# EP4CE6E22C8N.net
KiCad netlist of a schematic drawn in Altium Designer
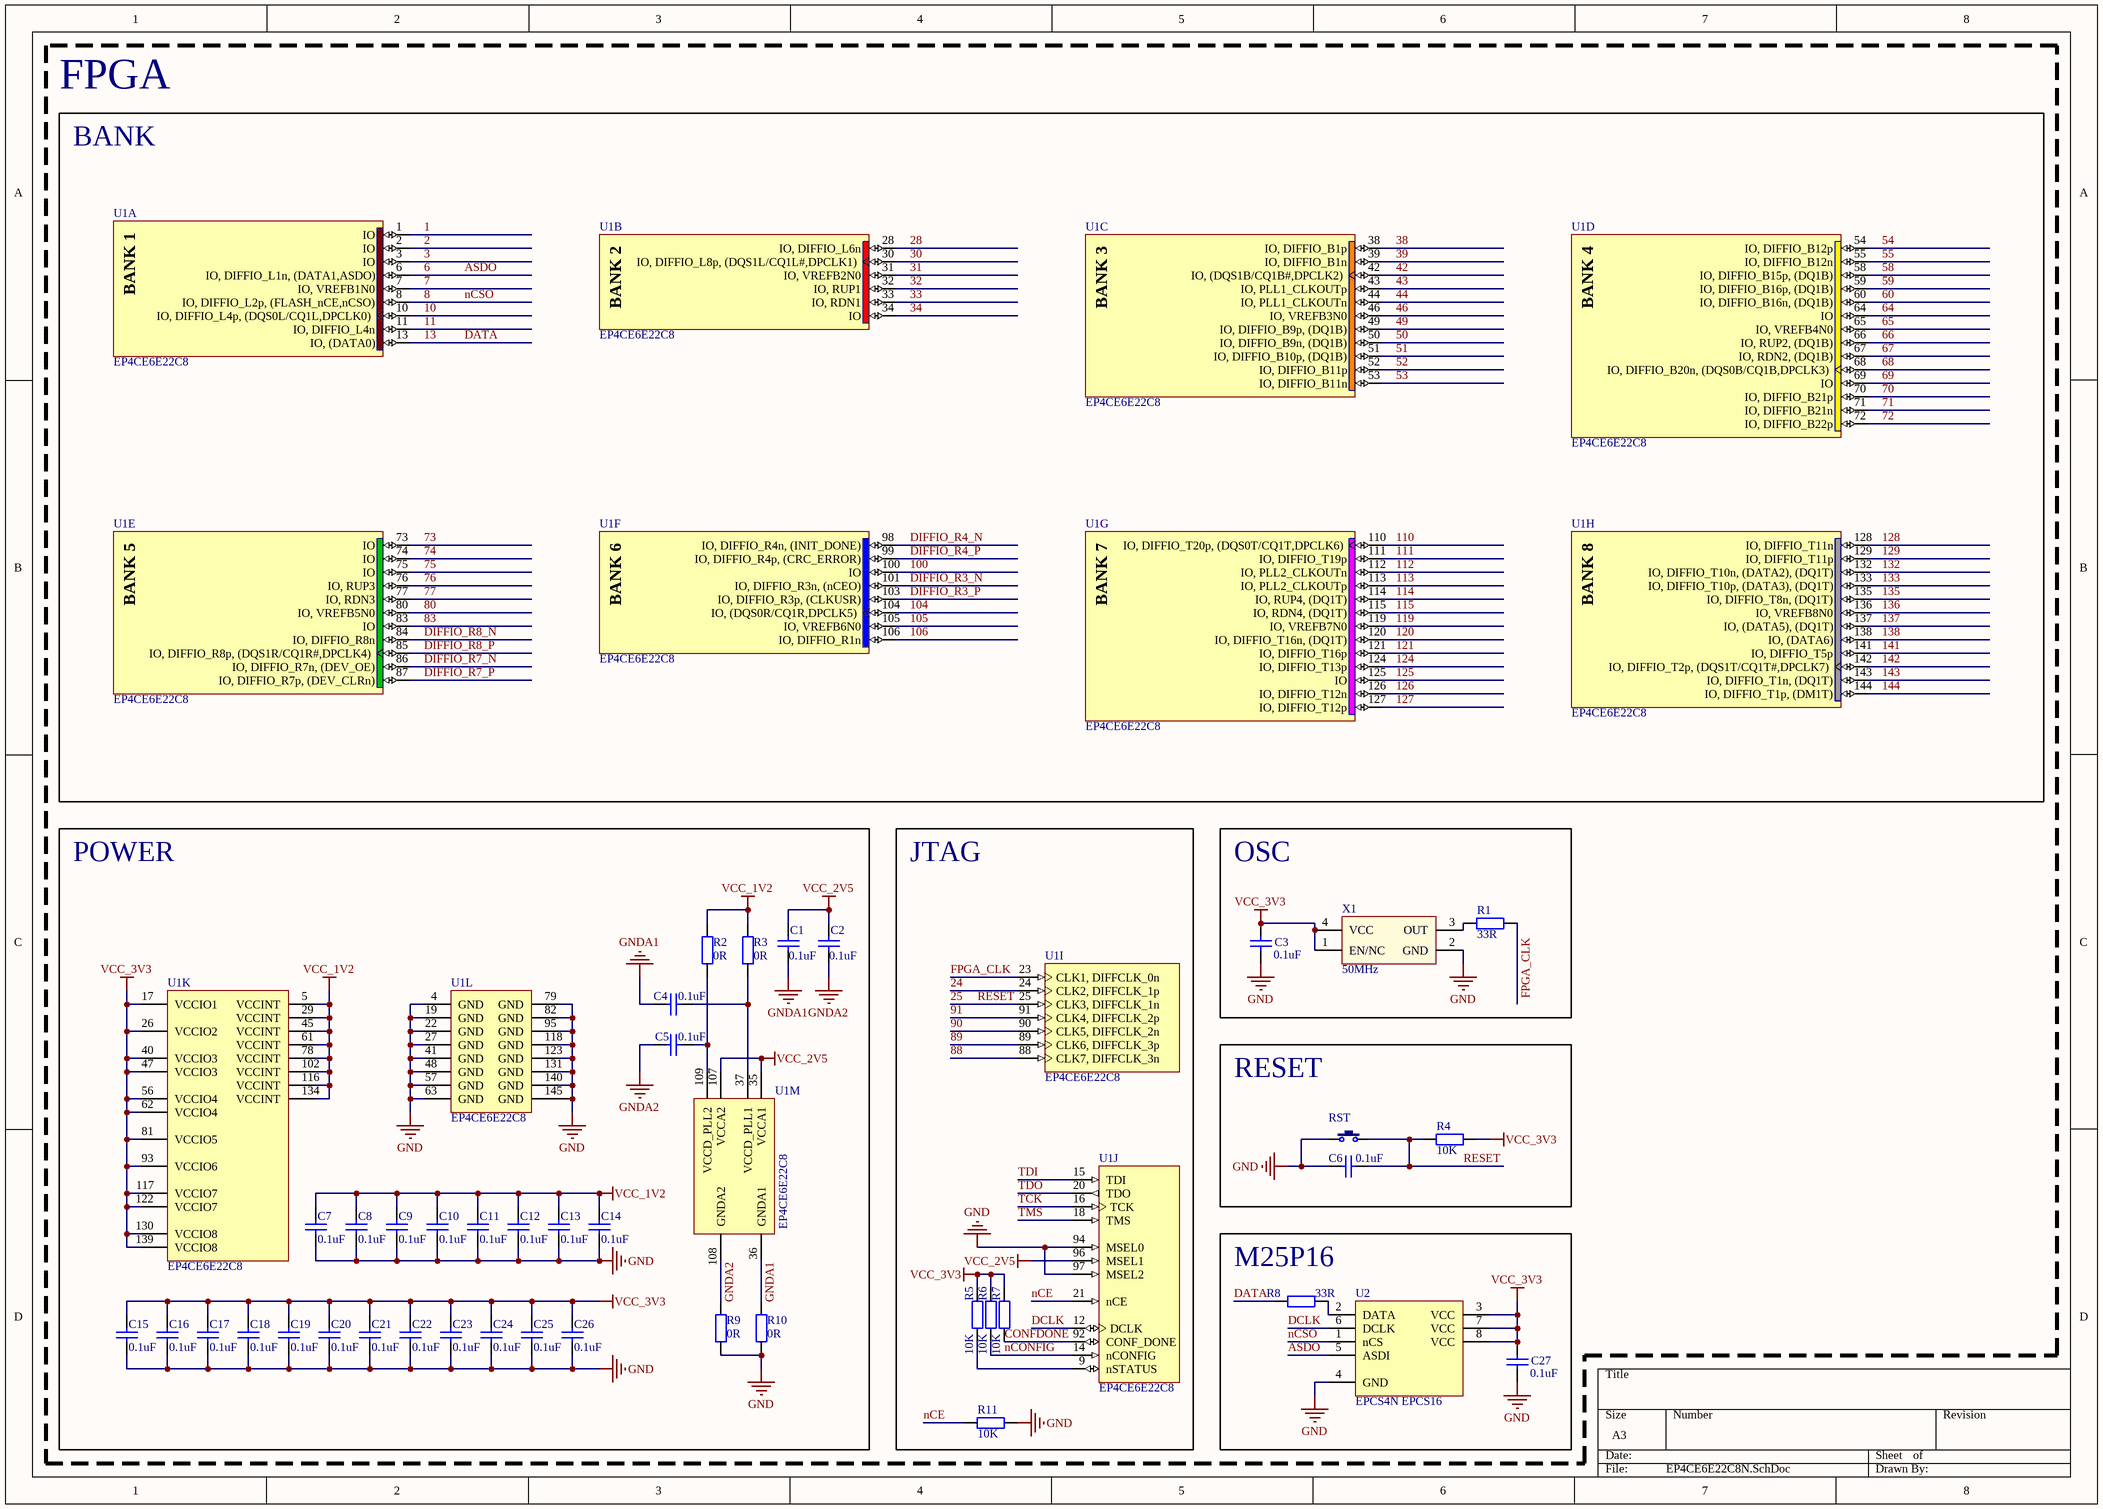
[diagram p0: EP4CE6E22C8N.SchDoc]

(export (version "E")
  (design (tool "Eeschema 10.0.6"))
  (components
    (comp (ref "C1")
      (value "0.1uF")
      (footprint "0402_C")
      (description "贴片电容")
      (libsource (lib "My_Devices") (part "0402_C"))
    )
    (comp (ref "C2")
      (value "0.1uF")
      (footprint "0402_C")
      (description "贴片电容")
      (libsource (lib "My_Devices") (part "0402_C"))
    )
    (comp (ref "C3")
      (value "0.1uF")
      (footprint "0402_C")
      (description "贴片电容")
      (libsource (lib "My_Devices") (part "0402_C"))
    )
    (comp (ref "C4")
      (value "0.1uF")
      (footprint "0402_C")
      (description "贴片电容")
      (libsource (lib "My_Devices") (part "0402_C"))
    )
    (comp (ref "C5")
      (value "0.1uF")
      (footprint "0402_C")
      (description "贴片电容")
      (libsource (lib "My_Devices") (part "0402_C"))
    )
    (comp (ref "C6")
      (value "0.1uF")
      (footprint "0402_C")
      (description "贴片电容")
      (libsource (lib "My_Devices") (part "0402_C"))
    )
    (comp (ref "C7")
      (value "0.1uF")
      (footprint "0402_C")
      (description "贴片电容")
      (libsource (lib "My_Devices") (part "0402_C"))
    )
    (comp (ref "C8")
      (value "0.1uF")
      (footprint "0402_C")
      (description "贴片电容")
      (libsource (lib "My_Devices") (part "0402_C"))
    )
    (comp (ref "C9")
      (value "0.1uF")
      (footprint "0402_C")
      (description "贴片电容")
      (libsource (lib "My_Devices") (part "0402_C"))
    )
    (comp (ref "C10")
      (value "0.1uF")
      (footprint "0402_C")
      (description "贴片电容")
      (libsource (lib "My_Devices") (part "0402_C"))
    )
    (comp (ref "C11")
      (value "0.1uF")
      (footprint "0402_C")
      (description "贴片电容")
      (libsource (lib "My_Devices") (part "0402_C"))
    )
    (comp (ref "C12")
      (value "0.1uF")
      (footprint "0402_C")
      (description "贴片电容")
      (libsource (lib "My_Devices") (part "0402_C"))
    )
    (comp (ref "C13")
      (value "0.1uF")
      (footprint "0402_C")
      (description "贴片电容")
      (libsource (lib "My_Devices") (part "0402_C"))
    )
    (comp (ref "C14")
      (value "0.1uF")
      (footprint "0402_C")
      (description "贴片电容")
      (libsource (lib "My_Devices") (part "0402_C"))
    )
    (comp (ref "C15")
      (value "0.1uF")
      (footprint "0402_C")
      (description "贴片电容")
      (libsource (lib "My_Devices") (part "0402_C"))
    )
    (comp (ref "C16")
      (value "0.1uF")
      (footprint "0402_C")
      (description "贴片电容")
      (libsource (lib "My_Devices") (part "0402_C"))
    )
    (comp (ref "C17")
      (value "0.1uF")
      (footprint "0402_C")
      (description "贴片电容")
      (libsource (lib "My_Devices") (part "0402_C"))
    )
    (comp (ref "C18")
      (value "0.1uF")
      (footprint "0402_C")
      (description "贴片电容")
      (libsource (lib "My_Devices") (part "0402_C"))
    )
    (comp (ref "C19")
      (value "0.1uF")
      (footprint "0402_C")
      (description "贴片电容")
      (libsource (lib "My_Devices") (part "0402_C"))
    )
    (comp (ref "C20")
      (value "0.1uF")
      (footprint "0402_C")
      (description "贴片电容")
      (libsource (lib "My_Devices") (part "0402_C"))
    )
    (comp (ref "C21")
      (value "0.1uF")
      (footprint "0402_C")
      (description "贴片电容")
      (libsource (lib "My_Devices") (part "0402_C"))
    )
    (comp (ref "C22")
      (value "0.1uF")
      (footprint "0402_C")
      (description "贴片电容")
      (libsource (lib "My_Devices") (part "0402_C"))
    )
    (comp (ref "C23")
      (value "0.1uF")
      (footprint "0402_C")
      (description "贴片电容")
      (libsource (lib "My_Devices") (part "0402_C"))
    )
    (comp (ref "C24")
      (value "0.1uF")
      (footprint "0402_C")
      (description "贴片电容")
      (libsource (lib "My_Devices") (part "0402_C"))
    )
    (comp (ref "C25")
      (value "0.1uF")
      (footprint "0402_C")
      (description "贴片电容")
      (libsource (lib "My_Devices") (part "0402_C"))
    )
    (comp (ref "C26")
      (value "0.1uF")
      (footprint "0402_C")
      (description "贴片电容")
      (libsource (lib "My_Devices") (part "0402_C"))
    )
    (comp (ref "C27")
      (value "0.1uF")
      (footprint "0402_C")
      (description "贴片电容")
      (libsource (lib "My_Devices") (part "0402_C"))
    )
    (comp (ref "R1")
      (value "33R")
      (footprint "0402_R")
      (description "贴片电阻")
      (libsource (lib "My_Devices") (part "0402_R"))
    )
    (comp (ref "R2")
      (value "0R")
      (footprint "0603_R _MINI")
      (description "贴片电阻")
      (libsource (lib "My_Devices") (part "0603_R_MINI"))
    )
    (comp (ref "R3")
      (value "0R")
      (footprint "0603_R _MINI")
      (description "贴片电阻")
      (libsource (lib "My_Devices") (part "0603_R_MINI"))
    )
    (comp (ref "R4")
      (value "10K")
      (footprint "0402_R")
      (description "贴片电阻")
      (libsource (lib "My_Devices") (part "0402_R"))
    )
    (comp (ref "R5")
      (value "10K")
      (footprint "0402_R")
      (description "贴片电阻")
      (libsource (lib "") (part "0402_R_1"))
    )
    (comp (ref "R6")
      (value "10K")
      (footprint "0402_R")
      (description "贴片电阻")
      (libsource (lib "") (part "0402_R_1"))
    )
    (comp (ref "R7")
      (value "10K")
      (footprint "0402_R")
      (description "贴片电阻")
      (libsource (lib "") (part "0402_R_1"))
    )
    (comp (ref "R8")
      (value "33R")
      (footprint "0402_R")
      (description "贴片电阻")
      (libsource (lib "My_Devices") (part "0402_R"))
    )
    (comp (ref "R9")
      (value "0R")
      (footprint "0603_R _MINI")
      (description "贴片电阻")
      (libsource (lib "My_Devices") (part "0603_R_MINI"))
    )
    (comp (ref "R10")
      (value "0R")
      (footprint "0603_R _MINI")
      (description "贴片电阻")
      (libsource (lib "My_Devices") (part "0603_R_MINI"))
    )
    (comp (ref "R11")
      (value "10K")
      (footprint "0402_R")
      (description "贴片电阻")
      (libsource (lib "My_Devices") (part "0402_R"))
    )
    (comp (ref "RST")
      (value "3x6x5")
      (footprint "SW")
      (description "3x6轻触开关")
      (fields (field (name "版权归属") "源创客"))
      (libsource (lib "My_Devices") (part "TSW 3x6"))
    )
    (comp (ref "U1")
      (value "EP4CE6E22C8")
      (footprint "EQFP144 20X20_N")
      (description "Cyclone IV Family FPGA, 2V Core, 91 I/O Pins, 2 PLLs, 144-Pin QFP, Speed Grade 8, Commercial Grade")
      (fields (field (name "PUBLISHER") "Altium Limited"))
      (libsource (lib "") (part "EP4CE6E22C8_1"))
    )
    (comp (ref "U2") (value "EPCS4N EPCS16") (footprint "SOP8_M") (libsource (lib "Schlib1") (part "EPCS1")))
    (comp (ref "X1")
      (value "50MHz")
      (footprint "OSC 7050-4P")
      (description "4脚有源晶振")
      (fields (field (name "版权归属") "源创客"))
      (libsource (lib "My_Devices") (part "XTAL-ACT-4P"))
    )
  )
  (nets
    (net (code "1") (name "/1") (class "Default")
      (node (ref "U1") (pin "1") (pinfunction "IO_1") (pintype "bidirectional"))
    )
    (net (code "2") (name "/2") (class "Default")
      (node (ref "U1") (pin "2") (pinfunction "IO_2") (pintype "bidirectional"))
    )
    (net (code "3") (name "/3") (class "Default")
      (node (ref "U1") (pin "3") (pinfunction "IO_3") (pintype "bidirectional"))
    )
    (net (code "4") (name "/6") (class "Default")
      (node (ref "U1") (pin "6") (pinfunction "IO,_DIFFIO_L1n,_(DATA1,ASDO)_6") (pintype "bidirectional"))
      (node (ref "U2") (pin "5") (pinfunction "ASDI_5") (pintype "passive"))
    )
    (net (code "5") (name "/7") (class "Default")
      (node (ref "U1") (pin "7") (pinfunction "IO,_VREFB1N0_7") (pintype "bidirectional"))
    )
    (net (code "6") (name "/8") (class "Default")
      (node (ref "U1") (pin "8") (pinfunction "IO,_DIFFIO_L2p,_(FLASH_nCE,nCSO)_8") (pintype "bidirectional"))
      (node (ref "U2") (pin "1") (pinfunction "nCS_1") (pintype "passive"))
    )
    (net (code "7") (name "/10") (class "Default")
      (node (ref "U1") (pin "10") (pinfunction "IO,_DIFFIO_L4p,_(DQS0L/CQ1L,DPCLK0)_10") (pintype "bidirectional"))
    )
    (net (code "8") (name "/11") (class "Default")
      (node (ref "U1") (pin "11") (pinfunction "IO,_DIFFIO_L4n_11") (pintype "bidirectional"))
    )
    (net (code "9") (name "/13") (class "Default")
      (node (ref "R8") (pin "1") (pinfunction "1_1") (pintype "passive"))
      (node (ref "U1") (pin "13") (pinfunction "IO,_(DATA0)_13") (pintype "bidirectional"))
    )
    (net (code "10") (name "/24") (class "Default")
      (node (ref "U1") (pin "24") (pinfunction "CLK2,_DIFFCLK_1p_24") (pintype "input"))
    )
    (net (code "11") (name "/25") (class "Default")
      (node (ref "C6") (pin "2") (pinfunction "2_2") (pintype "passive"))
      (node (ref "R4") (pin "1") (pinfunction "1_1") (pintype "passive"))
      (node (ref "RST") (pin "2") (pinfunction "2_2") (pintype "passive"))
      (node (ref "U1") (pin "25") (pinfunction "CLK3,_DIFFCLK_1n_25") (pintype "input"))
    )
    (net (code "12") (name "/28") (class "Default")
      (node (ref "U1") (pin "28") (pinfunction "IO,_DIFFIO_L6n_28") (pintype "bidirectional"))
    )
    (net (code "13") (name "/30") (class "Default")
      (node (ref "U1") (pin "30") (pinfunction "IO,_DIFFIO_L8p,_(DQS1L/CQ1L#,DPCLK1)_30") (pintype "bidirectional"))
    )
    (net (code "14") (name "/31") (class "Default")
      (node (ref "U1") (pin "31") (pinfunction "IO,_VREFB2N0_31") (pintype "bidirectional"))
    )
    (net (code "15") (name "/32") (class "Default")
      (node (ref "U1") (pin "32") (pinfunction "IO,_RUP1_32") (pintype "bidirectional"))
    )
    (net (code "16") (name "/33") (class "Default")
      (node (ref "U1") (pin "33") (pinfunction "IO,_RDN1_33") (pintype "bidirectional"))
    )
    (net (code "17") (name "/34") (class "Default")
      (node (ref "U1") (pin "34") (pinfunction "IO_34") (pintype "bidirectional"))
    )
    (net (code "18") (name "/38") (class "Default")
      (node (ref "U1") (pin "38") (pinfunction "IO,_DIFFIO_B1p_38") (pintype "bidirectional"))
    )
    (net (code "19") (name "/39") (class "Default")
      (node (ref "U1") (pin "39") (pinfunction "IO,_DIFFIO_B1n_39") (pintype "bidirectional"))
    )
    (net (code "20") (name "/42") (class "Default")
      (node (ref "U1") (pin "42") (pinfunction "IO,_(DQS1B/CQ1B#,DPCLK2)_42") (pintype "bidirectional"))
    )
    (net (code "21") (name "/43") (class "Default")
      (node (ref "U1") (pin "43") (pinfunction "IO,_PLL1_CLKOUTp_43") (pintype "bidirectional"))
    )
    (net (code "22") (name "/44") (class "Default")
      (node (ref "U1") (pin "44") (pinfunction "IO,_PLL1_CLKOUTn_44") (pintype "bidirectional"))
    )
    (net (code "23") (name "/46") (class "Default")
      (node (ref "U1") (pin "46") (pinfunction "IO,_VREFB3N0_46") (pintype "bidirectional"))
    )
    (net (code "24") (name "/49") (class "Default")
      (node (ref "U1") (pin "49") (pinfunction "IO,_DIFFIO_B9p,_(DQ1B)_49") (pintype "bidirectional"))
    )
    (net (code "25") (name "/50") (class "Default")
      (node (ref "U1") (pin "50") (pinfunction "IO,_DIFFIO_B9n,_(DQ1B)_50") (pintype "bidirectional"))
    )
    (net (code "26") (name "/51") (class "Default")
      (node (ref "U1") (pin "51") (pinfunction "IO,_DIFFIO_B10p,_(DQ1B)_51") (pintype "bidirectional"))
    )
    (net (code "27") (name "/52") (class "Default")
      (node (ref "U1") (pin "52") (pinfunction "IO,_DIFFIO_B11p_52") (pintype "bidirectional"))
    )
    (net (code "28") (name "/53") (class "Default")
      (node (ref "U1") (pin "53") (pinfunction "IO,_DIFFIO_B11n_53") (pintype "bidirectional"))
    )
    (net (code "29") (name "/54") (class "Default")
      (node (ref "U1") (pin "54") (pinfunction "IO,_DIFFIO_B12p_54") (pintype "bidirectional"))
    )
    (net (code "30") (name "/55") (class "Default")
      (node (ref "U1") (pin "55") (pinfunction "IO,_DIFFIO_B12n_55") (pintype "bidirectional"))
    )
    (net (code "31") (name "/58") (class "Default")
      (node (ref "U1") (pin "58") (pinfunction "IO,_DIFFIO_B15p,_(DQ1B)_58") (pintype "bidirectional"))
    )
    (net (code "32") (name "/59") (class "Default")
      (node (ref "U1") (pin "59") (pinfunction "IO,_DIFFIO_B16p,_(DQ1B)_59") (pintype "bidirectional"))
    )
    (net (code "33") (name "/60") (class "Default")
      (node (ref "U1") (pin "60") (pinfunction "IO,_DIFFIO_B16n,_(DQ1B)_60") (pintype "bidirectional"))
    )
    (net (code "34") (name "/64") (class "Default")
      (node (ref "U1") (pin "64") (pinfunction "IO_64") (pintype "bidirectional"))
    )
    (net (code "35") (name "/65") (class "Default")
      (node (ref "U1") (pin "65") (pinfunction "IO,_VREFB4N0_65") (pintype "bidirectional"))
    )
    (net (code "36") (name "/66") (class "Default")
      (node (ref "U1") (pin "66") (pinfunction "IO,_RUP2,_(DQ1B)_66") (pintype "bidirectional"))
    )
    (net (code "37") (name "/67") (class "Default")
      (node (ref "U1") (pin "67") (pinfunction "IO,_RDN2,_(DQ1B)_67") (pintype "bidirectional"))
    )
    (net (code "38") (name "/68") (class "Default")
      (node (ref "U1") (pin "68") (pinfunction "IO,_DIFFIO_B20n,_(DQS0B/CQ1B,DPCLK3)_68") (pintype "bidirectional"))
    )
    (net (code "39") (name "/69") (class "Default")
      (node (ref "U1") (pin "69") (pinfunction "IO_69") (pintype "bidirectional"))
    )
    (net (code "40") (name "/70") (class "Default")
      (node (ref "U1") (pin "70") (pinfunction "IO,_DIFFIO_B21p_70") (pintype "bidirectional"))
    )
    (net (code "41") (name "/71") (class "Default")
      (node (ref "U1") (pin "71") (pinfunction "IO,_DIFFIO_B21n_71") (pintype "bidirectional"))
    )
    (net (code "42") (name "/72") (class "Default")
      (node (ref "U1") (pin "72") (pinfunction "IO,_DIFFIO_B22p_72") (pintype "bidirectional"))
    )
    (net (code "43") (name "/73") (class "Default")
      (node (ref "U1") (pin "73") (pinfunction "IO_73") (pintype "bidirectional"))
    )
    (net (code "44") (name "/74") (class "Default")
      (node (ref "U1") (pin "74") (pinfunction "IO_74") (pintype "bidirectional"))
    )
    (net (code "45") (name "/75") (class "Default")
      (node (ref "U1") (pin "75") (pinfunction "IO_75") (pintype "bidirectional"))
    )
    (net (code "46") (name "/76") (class "Default")
      (node (ref "U1") (pin "76") (pinfunction "IO,_RUP3_76") (pintype "bidirectional"))
    )
    (net (code "47") (name "/77") (class "Default")
      (node (ref "U1") (pin "77") (pinfunction "IO,_RDN3_77") (pintype "bidirectional"))
    )
    (net (code "48") (name "/80") (class "Default")
      (node (ref "U1") (pin "80") (pinfunction "IO,_VREFB5N0_80") (pintype "bidirectional"))
    )
    (net (code "49") (name "/83") (class "Default")
      (node (ref "U1") (pin "83") (pinfunction "IO_83") (pintype "bidirectional"))
    )
    (net (code "50") (name "/88") (class "Default")
      (node (ref "U1") (pin "88") (pinfunction "CLK7,_DIFFCLK_3n_88") (pintype "input"))
    )
    (net (code "51") (name "/89") (class "Default")
      (node (ref "U1") (pin "89") (pinfunction "CLK6,_DIFFCLK_3p_89") (pintype "input"))
    )
    (net (code "52") (name "/90") (class "Default")
      (node (ref "U1") (pin "90") (pinfunction "CLK5,_DIFFCLK_2n_90") (pintype "input"))
    )
    (net (code "53") (name "/91") (class "Default")
      (node (ref "U1") (pin "91") (pinfunction "CLK4,_DIFFCLK_2p_91") (pintype "input"))
    )
    (net (code "54") (name "/100") (class "Default")
      (node (ref "U1") (pin "100") (pinfunction "IO_100") (pintype "bidirectional"))
    )
    (net (code "55") (name "/104") (class "Default")
      (node (ref "U1") (pin "104") (pinfunction "IO,_(DQS0R/CQ1R,DPCLK5)_104") (pintype "bidirectional"))
    )
    (net (code "56") (name "/105") (class "Default")
      (node (ref "U1") (pin "105") (pinfunction "IO,_VREFB6N0_105") (pintype "bidirectional"))
    )
    (net (code "57") (name "/106") (class "Default")
      (node (ref "U1") (pin "106") (pinfunction "IO,_DIFFIO_R1n_106") (pintype "bidirectional"))
    )
    (net (code "58") (name "/110") (class "Default")
      (node (ref "U1") (pin "110") (pinfunction "IO,_DIFFIO_T20p,_(DQS0T/CQ1T,DPCLK6)_110") (pintype "bidirectional"))
    )
    (net (code "59") (name "/111") (class "Default")
      (node (ref "U1") (pin "111") (pinfunction "IO,_DIFFIO_T19p_111") (pintype "bidirectional"))
    )
    (net (code "60") (name "/112") (class "Default")
      (node (ref "U1") (pin "112") (pinfunction "IO,_PLL2_CLKOUTn_112") (pintype "bidirectional"))
    )
    (net (code "61") (name "/113") (class "Default")
      (node (ref "U1") (pin "113") (pinfunction "IO,_PLL2_CLKOUTp_113") (pintype "bidirectional"))
    )
    (net (code "62") (name "/114") (class "Default")
      (node (ref "U1") (pin "114") (pinfunction "IO,_RUP4,_(DQ1T)_114") (pintype "bidirectional"))
    )
    (net (code "63") (name "/115") (class "Default")
      (node (ref "U1") (pin "115") (pinfunction "IO,_RDN4,_(DQ1T)_115") (pintype "bidirectional"))
    )
    (net (code "64") (name "/119") (class "Default")
      (node (ref "U1") (pin "119") (pinfunction "IO,_VREFB7N0_119") (pintype "bidirectional"))
    )
    (net (code "65") (name "/120") (class "Default")
      (node (ref "U1") (pin "120") (pinfunction "IO,_DIFFIO_T16n,_(DQ1T)_120") (pintype "bidirectional"))
    )
    (net (code "66") (name "/121") (class "Default")
      (node (ref "U1") (pin "121") (pinfunction "IO,_DIFFIO_T16p_121") (pintype "bidirectional"))
    )
    (net (code "67") (name "/124") (class "Default")
      (node (ref "U1") (pin "124") (pinfunction "IO,_DIFFIO_T13p_124") (pintype "bidirectional"))
    )
    (net (code "68") (name "/125") (class "Default")
      (node (ref "U1") (pin "125") (pinfunction "IO_125") (pintype "bidirectional"))
    )
    (net (code "69") (name "/126") (class "Default")
      (node (ref "U1") (pin "126") (pinfunction "IO,_DIFFIO_T12n_126") (pintype "bidirectional"))
    )
    (net (code "70") (name "/127") (class "Default")
      (node (ref "U1") (pin "127") (pinfunction "IO,_DIFFIO_T12p_127") (pintype "bidirectional"))
    )
    (net (code "71") (name "/128") (class "Default")
      (node (ref "U1") (pin "128") (pinfunction "IO,_DIFFIO_T11n_128") (pintype "bidirectional"))
    )
    (net (code "72") (name "/129") (class "Default")
      (node (ref "U1") (pin "129") (pinfunction "IO,_DIFFIO_T11p_129") (pintype "bidirectional"))
    )
    (net (code "73") (name "/132") (class "Default")
      (node (ref "U1") (pin "132") (pinfunction "IO,_DIFFIO_T10n,_(DATA2),_(DQ1T)_132") (pintype "bidirectional"))
    )
    (net (code "74") (name "/133") (class "Default")
      (node (ref "U1") (pin "133") (pinfunction "IO,_DIFFIO_T10p,_(DATA3),_(DQ1T)_133") (pintype "bidirectional"))
    )
    (net (code "75") (name "/135") (class "Default")
      (node (ref "U1") (pin "135") (pinfunction "IO,_DIFFIO_T8n,_(DQ1T)_135") (pintype "bidirectional"))
    )
    (net (code "76") (name "/136") (class "Default")
      (node (ref "U1") (pin "136") (pinfunction "IO,_VREFB8N0_136") (pintype "bidirectional"))
    )
    (net (code "77") (name "/137") (class "Default")
      (node (ref "U1") (pin "137") (pinfunction "IO,_(DATA5),_(DQ1T)_137") (pintype "bidirectional"))
    )
    (net (code "78") (name "/138") (class "Default")
      (node (ref "U1") (pin "138") (pinfunction "IO,_(DATA6)_138") (pintype "bidirectional"))
    )
    (net (code "79") (name "/141") (class "Default")
      (node (ref "U1") (pin "141") (pinfunction "IO,_DIFFIO_T5p_141") (pintype "bidirectional"))
    )
    (net (code "80") (name "/142") (class "Default")
      (node (ref "U1") (pin "142") (pinfunction "IO,_DIFFIO_T2p,_(DQS1T/CQ1T#,DPCLK7)_142") (pintype "bidirectional"))
    )
    (net (code "81") (name "/143") (class "Default")
      (node (ref "U1") (pin "143") (pinfunction "IO,_DIFFIO_T1n,_(DQ1T)_143") (pintype "bidirectional"))
    )
    (net (code "82") (name "/144") (class "Default")
      (node (ref "U1") (pin "144") (pinfunction "IO,_DIFFIO_T1p,_(DM1T)_144") (pintype "bidirectional"))
    )
    (net (code "83") (name "/CONFDONE") (class "Default")
      (node (ref "R7") (pin "2") (pinfunction "2_2") (pintype "passive"))
      (node (ref "U1") (pin "92") (pinfunction "CONF_DONE_92") (pintype "bidirectional"))
    )
    (net (code "84") (name "/DCLK") (class "Default")
      (node (ref "U1") (pin "12") (pinfunction "DCLK_12") (pintype "bidirectional"))
      (node (ref "U2") (pin "6") (pinfunction "DCLK_6") (pintype "passive"))
    )
    (net (code "85") (name "/DIFFIO_R3_N") (class "Default")
      (node (ref "U1") (pin "101") (pinfunction "IO,_DIFFIO_R3n,_(nCEO)_101") (pintype "bidirectional"))
    )
    (net (code "86") (name "/DIFFIO_R3_P") (class "Default")
      (node (ref "U1") (pin "103") (pinfunction "IO,_DIFFIO_R3p,_(CLKUSR)_103") (pintype "bidirectional"))
    )
    (net (code "87") (name "/DIFFIO_R4_N") (class "Default")
      (node (ref "U1") (pin "98") (pinfunction "IO,_DIFFIO_R4n,_(INIT_DONE)_98") (pintype "bidirectional"))
    )
    (net (code "88") (name "/DIFFIO_R4_P") (class "Default")
      (node (ref "U1") (pin "99") (pinfunction "IO,_DIFFIO_R4p,_(CRC_ERROR)_99") (pintype "bidirectional"))
    )
    (net (code "89") (name "/DIFFIO_R7_N") (class "Default")
      (node (ref "U1") (pin "86") (pinfunction "IO,_DIFFIO_R7n,_(DEV_OE)_86") (pintype "bidirectional"))
    )
    (net (code "90") (name "/DIFFIO_R7_P") (class "Default")
      (node (ref "U1") (pin "87") (pinfunction "IO,_DIFFIO_R7p,_(DEV_CLRn)_87") (pintype "bidirectional"))
    )
    (net (code "91") (name "/DIFFIO_R8_N") (class "Default")
      (node (ref "U1") (pin "84") (pinfunction "IO,_DIFFIO_R8n_84") (pintype "bidirectional"))
    )
    (net (code "92") (name "/DIFFIO_R8_P") (class "Default")
      (node (ref "U1") (pin "85") (pinfunction "IO,_DIFFIO_R8p,_(DQS1R/CQ1R#,DPCLK4)_85") (pintype "bidirectional"))
    )
    (net (code "93") (name "/FPGA_CLK") (class "Default")
      (node (ref "R1") (pin "2") (pinfunction "2_2") (pintype "passive"))
      (node (ref "U1") (pin "23") (pinfunction "CLK1,_DIFFCLK_0n_23") (pintype "input"))
    )
    (net (code "94") (name "/TCK") (class "Default")
      (node (ref "U1") (pin "16") (pinfunction "TCK_16") (pintype "input"))
    )
    (net (code "95") (name "/TDI") (class "Default")
      (node (ref "U1") (pin "15") (pinfunction "TDI_15") (pintype "input"))
    )
    (net (code "96") (name "/TDO") (class "Default")
      (node (ref "U1") (pin "20") (pinfunction "TDO_20") (pintype "output"))
    )
    (net (code "97") (name "/TMS") (class "Default")
      (node (ref "U1") (pin "18") (pinfunction "TMS_18") (pintype "input"))
    )
    (net (code "98") (name "/nCE") (class "Default")
      (node (ref "R11") (pin "1") (pinfunction "1_1") (pintype "passive"))
      (node (ref "U1") (pin "21") (pinfunction "nCE_21") (pintype "input"))
    )
    (net (code "99") (name "/nCONFIG") (class "Default")
      (node (ref "R6") (pin "2") (pinfunction "2_2") (pintype "passive"))
      (node (ref "U1") (pin "14") (pinfunction "nCONFIG_14") (pintype "input"))
    )
    (net (code "100") (name "GND") (class "Default")
      (node (ref "C10") (pin "1") (pinfunction "1_1") (pintype "passive"))
      (node (ref "C11") (pin "1") (pinfunction "1_1") (pintype "passive"))
      (node (ref "C12") (pin "1") (pinfunction "1_1") (pintype "passive"))
      (node (ref "C13") (pin "1") (pinfunction "1_1") (pintype "passive"))
      (node (ref "C14") (pin "1") (pinfunction "1_1") (pintype "passive"))
      (node (ref "C15") (pin "1") (pinfunction "1_1") (pintype "passive"))
      (node (ref "C16") (pin "1") (pinfunction "1_1") (pintype "passive"))
      (node (ref "C17") (pin "1") (pinfunction "1_1") (pintype "passive"))
      (node (ref "C18") (pin "1") (pinfunction "1_1") (pintype "passive"))
      (node (ref "C19") (pin "1") (pinfunction "1_1") (pintype "passive"))
      (node (ref "C20") (pin "1") (pinfunction "1_1") (pintype "passive"))
      (node (ref "C21") (pin "1") (pinfunction "1_1") (pintype "passive"))
      (node (ref "C22") (pin "1") (pinfunction "1_1") (pintype "passive"))
      (node (ref "C23") (pin "1") (pinfunction "1_1") (pintype "passive"))
      (node (ref "C24") (pin "1") (pinfunction "1_1") (pintype "passive"))
      (node (ref "C25") (pin "1") (pinfunction "1_1") (pintype "passive"))
      (node (ref "C26") (pin "1") (pinfunction "1_1") (pintype "passive"))
      (node (ref "C27") (pin "1") (pinfunction "1_1") (pintype "passive"))
      (node (ref "C3") (pin "1") (pinfunction "1_1") (pintype "passive"))
      (node (ref "C6") (pin "1") (pinfunction "1_1") (pintype "passive"))
      (node (ref "C7") (pin "1") (pinfunction "1_1") (pintype "passive"))
      (node (ref "C8") (pin "1") (pinfunction "1_1") (pintype "passive"))
      (node (ref "C9") (pin "1") (pinfunction "1_1") (pintype "passive"))
      (node (ref "R10") (pin "2") (pinfunction "2_2") (pintype "passive"))
      (node (ref "R11") (pin "2") (pinfunction "2_2") (pintype "passive"))
      (node (ref "R9") (pin "2") (pinfunction "2_2") (pintype "passive"))
      (node (ref "RST") (pin "1") (pinfunction "1_1") (pintype "passive"))
      (node (ref "U1") (pin "118") (pinfunction "GND_118") (pintype "power_in"))
      (node (ref "U1") (pin "123") (pinfunction "GND_123") (pintype "power_in"))
      (node (ref "U1") (pin "131") (pinfunction "GND_131") (pintype "power_in"))
      (node (ref "U1") (pin "140") (pinfunction "GND_140") (pintype "power_in"))
      (node (ref "U1") (pin "145") (pinfunction "GND_145") (pintype "passive"))
      (node (ref "U1") (pin "19") (pinfunction "GND_19") (pintype "power_in"))
      (node (ref "U1") (pin "22") (pinfunction "GND_22") (pintype "power_in"))
      (node (ref "U1") (pin "27") (pinfunction "GND_27") (pintype "power_in"))
      (node (ref "U1") (pin "4") (pinfunction "GND_4") (pintype "power_in"))
      (node (ref "U1") (pin "41") (pinfunction "GND_41") (pintype "power_in"))
      (node (ref "U1") (pin "48") (pinfunction "GND_48") (pintype "power_in"))
      (node (ref "U1") (pin "57") (pinfunction "GND_57") (pintype "power_in"))
      (node (ref "U1") (pin "63") (pinfunction "GND_63") (pintype "power_in"))
      (node (ref "U1") (pin "79") (pinfunction "GND_79") (pintype "power_in"))
      (node (ref "U1") (pin "82") (pinfunction "GND_82") (pintype "power_in"))
      (node (ref "U1") (pin "94") (pinfunction "MSEL0_94") (pintype "input"))
      (node (ref "U1") (pin "95") (pinfunction "GND_95") (pintype "power_in"))
      (node (ref "U1") (pin "97") (pinfunction "MSEL2_97") (pintype "input"))
      (node (ref "U2") (pin "4") (pinfunction "GND_4") (pintype "passive"))
      (node (ref "X1") (pin "2") (pinfunction "GND_2") (pintype "passive"))
    )
    (net (code "101") (name "GNDA1") (class "Default")
      (node (ref "C1") (pin "1") (pinfunction "1_1") (pintype "passive"))
      (node (ref "C4") (pin "1") (pinfunction "1_1") (pintype "passive"))
      (node (ref "R10") (pin "1") (pinfunction "1_1") (pintype "passive"))
      (node (ref "U1") (pin "36") (pinfunction "GNDA1_36") (pintype "power_in"))
    )
    (net (code "102") (name "GNDA2") (class "Default")
      (node (ref "C2") (pin "1") (pinfunction "1_1") (pintype "passive"))
      (node (ref "C5") (pin "1") (pinfunction "1_1") (pintype "passive"))
      (node (ref "R9") (pin "1") (pinfunction "1_1") (pintype "passive"))
      (node (ref "U1") (pin "108") (pinfunction "GNDA2_108") (pintype "power_in"))
    )
    (net (code "103") (name "Net-(U1J-nSTATUS)") (class "Default")
      (node (ref "R5") (pin "2") (pinfunction "2_2") (pintype "passive"))
      (node (ref "U1") (pin "9") (pinfunction "nSTATUS_9") (pintype "bidirectional"))
    )
    (net (code "104") (name "Net-(U1M-VCCD_PLL1)") (class "Default")
      (node (ref "C4") (pin "2") (pinfunction "2_2") (pintype "passive"))
      (node (ref "R3") (pin "2") (pinfunction "2_2") (pintype "passive"))
      (node (ref "U1") (pin "37") (pinfunction "VCCD_PLL1_37") (pintype "power_in"))
    )
    (net (code "105") (name "Net-(U1M-VCCD_PLL2)") (class "Default")
      (node (ref "C5") (pin "2") (pinfunction "2_2") (pintype "passive"))
      (node (ref "R2") (pin "2") (pinfunction "2_2") (pintype "passive"))
      (node (ref "U1") (pin "109") (pinfunction "VCCD_PLL2_109") (pintype "power_in"))
    )
    (net (code "106") (name "Net-(U2-DATA)") (class "Default")
      (node (ref "R8") (pin "2") (pinfunction "2_2") (pintype "passive"))
      (node (ref "U2") (pin "2") (pinfunction "DATA_2") (pintype "passive"))
    )
    (net (code "107") (name "Net-(X1-OUT)") (class "Default")
      (node (ref "R1") (pin "1") (pinfunction "1_1") (pintype "passive"))
      (node (ref "X1") (pin "3") (pinfunction "OUT_3") (pintype "passive"))
    )
    (net (code "108") (name "VCC_1V2") (class "Default")
      (node (ref "C10") (pin "2") (pinfunction "2_2") (pintype "passive"))
      (node (ref "C11") (pin "2") (pinfunction "2_2") (pintype "passive"))
      (node (ref "C12") (pin "2") (pinfunction "2_2") (pintype "passive"))
      (node (ref "C13") (pin "2") (pinfunction "2_2") (pintype "passive"))
      (node (ref "C14") (pin "2") (pinfunction "2_2") (pintype "passive"))
      (node (ref "C7") (pin "2") (pinfunction "2_2") (pintype "passive"))
      (node (ref "C8") (pin "2") (pinfunction "2_2") (pintype "passive"))
      (node (ref "C9") (pin "2") (pinfunction "2_2") (pintype "passive"))
      (node (ref "R2") (pin "1") (pinfunction "1_1") (pintype "passive"))
      (node (ref "R3") (pin "1") (pinfunction "1_1") (pintype "passive"))
      (node (ref "U1") (pin "102") (pinfunction "VCCINT_102") (pintype "power_in"))
      (node (ref "U1") (pin "116") (pinfunction "VCCINT_116") (pintype "power_in"))
      (node (ref "U1") (pin "134") (pinfunction "VCCINT_134") (pintype "power_in"))
      (node (ref "U1") (pin "29") (pinfunction "VCCINT_29") (pintype "power_in"))
      (node (ref "U1") (pin "45") (pinfunction "VCCINT_45") (pintype "power_in"))
      (node (ref "U1") (pin "5") (pinfunction "VCCINT_5") (pintype "power_in"))
      (node (ref "U1") (pin "61") (pinfunction "VCCINT_61") (pintype "power_in"))
      (node (ref "U1") (pin "78") (pinfunction "VCCINT_78") (pintype "power_in"))
    )
    (net (code "109") (name "VCC_2V5") (class "Default")
      (node (ref "C1") (pin "2") (pinfunction "2_2") (pintype "passive"))
      (node (ref "C2") (pin "2") (pinfunction "2_2") (pintype "passive"))
      (node (ref "U1") (pin "107") (pinfunction "VCCA2_107") (pintype "power_in"))
      (node (ref "U1") (pin "35") (pinfunction "VCCA1_35") (pintype "power_in"))
      (node (ref "U1") (pin "96") (pinfunction "MSEL1_96") (pintype "input"))
    )
    (net (code "110") (name "VCC_3V3") (class "Default")
      (node (ref "C15") (pin "2") (pinfunction "2_2") (pintype "passive"))
      (node (ref "C16") (pin "2") (pinfunction "2_2") (pintype "passive"))
      (node (ref "C17") (pin "2") (pinfunction "2_2") (pintype "passive"))
      (node (ref "C18") (pin "2") (pinfunction "2_2") (pintype "passive"))
      (node (ref "C19") (pin "2") (pinfunction "2_2") (pintype "passive"))
      (node (ref "C20") (pin "2") (pinfunction "2_2") (pintype "passive"))
      (node (ref "C21") (pin "2") (pinfunction "2_2") (pintype "passive"))
      (node (ref "C22") (pin "2") (pinfunction "2_2") (pintype "passive"))
      (node (ref "C23") (pin "2") (pinfunction "2_2") (pintype "passive"))
      (node (ref "C24") (pin "2") (pinfunction "2_2") (pintype "passive"))
      (node (ref "C25") (pin "2") (pinfunction "2_2") (pintype "passive"))
      (node (ref "C26") (pin "2") (pinfunction "2_2") (pintype "passive"))
      (node (ref "C27") (pin "2") (pinfunction "2_2") (pintype "passive"))
      (node (ref "C3") (pin "2") (pinfunction "2_2") (pintype "passive"))
      (node (ref "R4") (pin "2") (pinfunction "2_2") (pintype "passive"))
      (node (ref "R5") (pin "1") (pinfunction "1_1") (pintype "passive"))
      (node (ref "R6") (pin "1") (pinfunction "1_1") (pintype "passive"))
      (node (ref "R7") (pin "1") (pinfunction "1_1") (pintype "passive"))
      (node (ref "U1") (pin "117") (pinfunction "VCCIO7_117") (pintype "power_in"))
      (node (ref "U1") (pin "122") (pinfunction "VCCIO7_122") (pintype "power_in"))
      (node (ref "U1") (pin "130") (pinfunction "VCCIO8_130") (pintype "power_in"))
      (node (ref "U1") (pin "139") (pinfunction "VCCIO8_139") (pintype "power_in"))
      (node (ref "U1") (pin "17") (pinfunction "VCCIO1_17") (pintype "power_in"))
      (node (ref "U1") (pin "26") (pinfunction "VCCIO2_26") (pintype "power_in"))
      (node (ref "U1") (pin "40") (pinfunction "VCCIO3_40") (pintype "power_in"))
      (node (ref "U1") (pin "47") (pinfunction "VCCIO3_47") (pintype "power_in"))
      (node (ref "U1") (pin "56") (pinfunction "VCCIO4_56") (pintype "power_in"))
      (node (ref "U1") (pin "62") (pinfunction "VCCIO4_62") (pintype "power_in"))
      (node (ref "U1") (pin "81") (pinfunction "VCCIO5_81") (pintype "power_in"))
      (node (ref "U1") (pin "93") (pinfunction "VCCIO6_93") (pintype "power_in"))
      (node (ref "U2") (pin "3") (pinfunction "VCC_3") (pintype "passive"))
      (node (ref "U2") (pin "7") (pinfunction "VCC_7") (pintype "passive"))
      (node (ref "U2") (pin "8") (pinfunction "VCC_8") (pintype "passive"))
      (node (ref "X1") (pin "1") (pinfunction "EN/NC_1") (pintype "passive"))
      (node (ref "X1") (pin "4") (pinfunction "VCC_4") (pintype "passive"))
    )
  )
)
